# PowerSupplies.net
KiCad netlist of a schematic drawn in Altium Designer
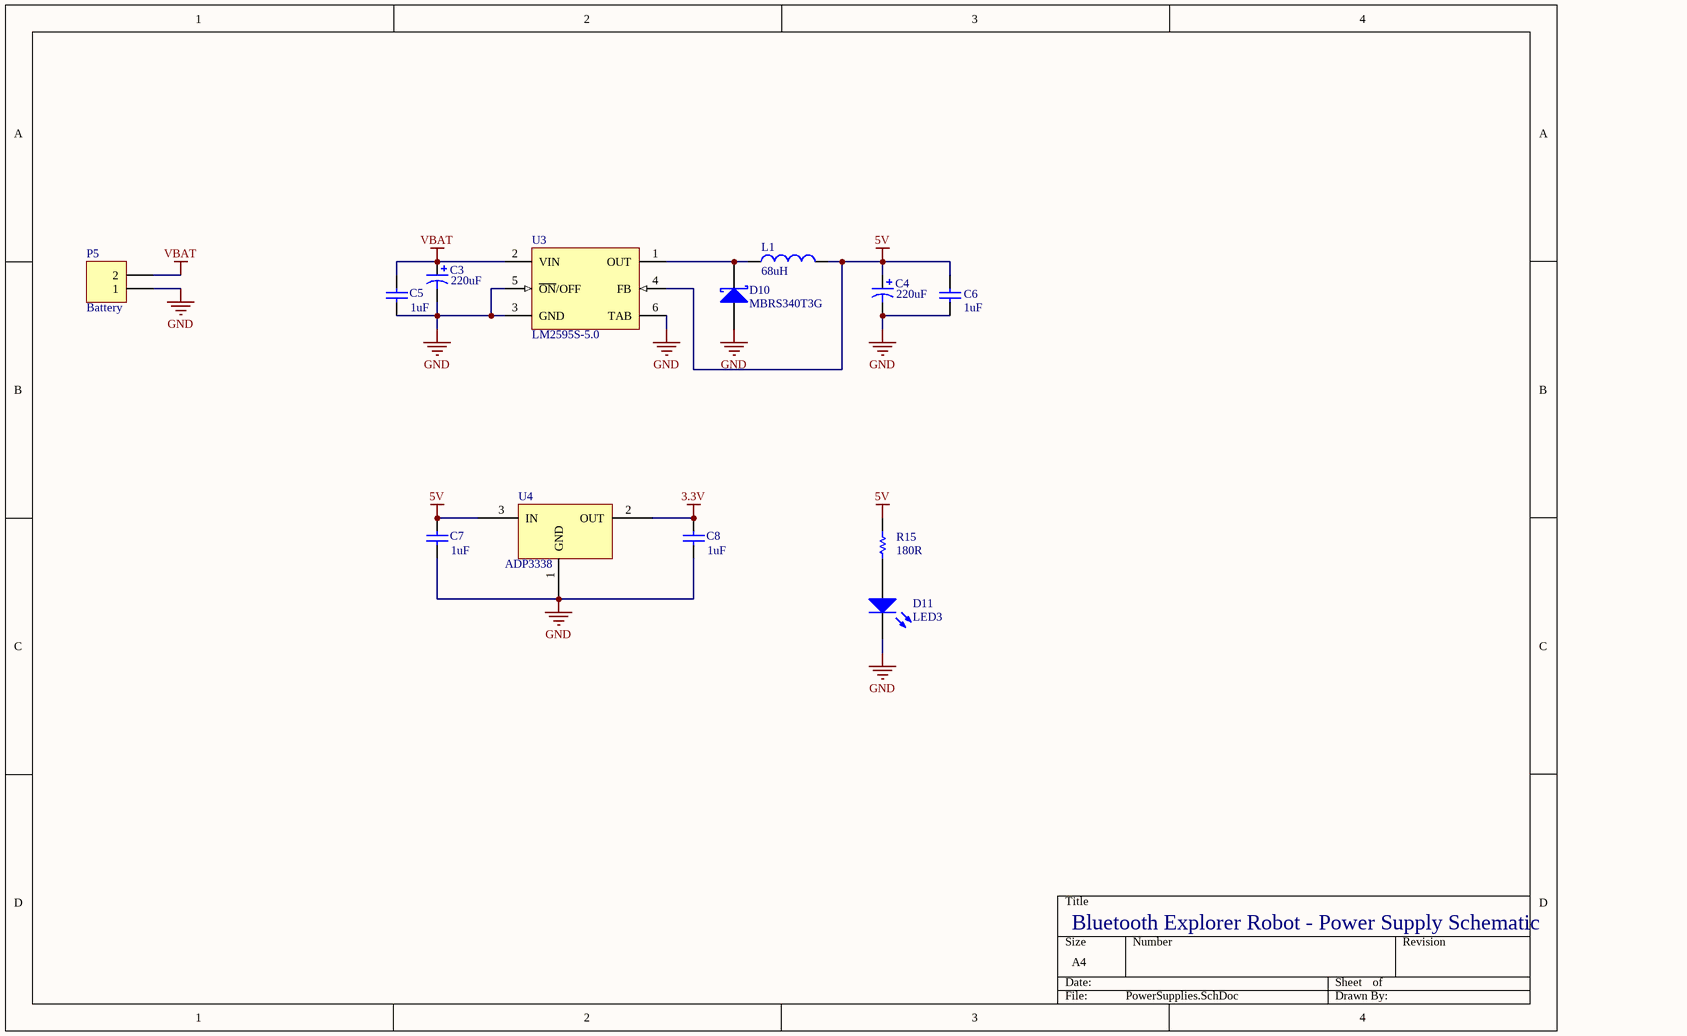
[diagram p0: PowerSupplies.SchDoc]

(export (version "E")
  (design (tool "Eeschema 10.0.6"))
  (components
    (comp (ref "C3")
      (value "220uF")
      (footprint "Cap F")
      (description "Polarized Capacitor (Radial)")
      (fields (field (name "Comment") "Cap Pol1") (field (name "PUBLISHER") "Altium Limited"))
      (libsource (lib "Miscellaneous Devices") (part "Cap Pol1"))
    )
    (comp (ref "C4")
      (value "220uF")
      (footprint "Cap F")
      (description "Polarized Capacitor (Radial)")
      (fields (field (name "Comment") "Cap Pol1") (field (name "PUBLISHER") "Altium Limited"))
      (libsource (lib "Miscellaneous Devices") (part "Cap Pol1"))
    )
    (comp (ref "C5")
      (value "1uF")
      (footprint "C0805")
      (description "Capacitor (Semiconductor SIM Model)")
      (fields (field (name "Comment") "Cap Semi") (field (name "PUBLISHER") "Altium Limited"))
      (libsource (lib "Miscellaneous Devices") (part "Cap Semi"))
    )
    (comp (ref "C6")
      (value "1uF")
      (footprint "C0805")
      (description "Capacitor (Semiconductor SIM Model)")
      (fields (field (name "Comment") "Cap Semi") (field (name "PUBLISHER") "Altium Limited"))
      (libsource (lib "Miscellaneous Devices") (part "Cap Semi"))
    )
    (comp (ref "C7")
      (value "1uF")
      (footprint "C0805")
      (description "Capacitor (Semiconductor SIM Model)")
      (fields (field (name "Comment") "Cap Semi") (field (name "PUBLISHER") "Altium Limited"))
      (libsource (lib "Miscellaneous Devices") (part "Cap Semi"))
    )
    (comp (ref "C8")
      (value "1uF")
      (footprint "C0805")
      (description "Capacitor (Semiconductor SIM Model)")
      (fields (field (name "Comment") "Cap Semi") (field (name "PUBLISHER") "Altium Limited"))
      (libsource (lib "Miscellaneous Devices") (part "Cap Semi"))
    )
    (comp (ref "D10")
      (value "MBRS340T3G")
      (footprint "SMC")
      (description "Schottky Diode")
      (fields (field (name "PUBLISHER") "Altium Limited"))
      (libsource (lib "Miscellaneous Devices") (part "D Schottky"))
    )
    (comp (ref "D11")
      (value "LED3")
      (footprint "DSO-C2/D5.6")
      (description "Typical BLUE SiC LED")
      (fields (field (name "PUBLISHER") "Altium Limited"))
      (libsource (lib "Miscellaneous Devices") (part "LED3"))
    )
    (comp (ref "L1")
      (value "68uH")
      (footprint "inductor_epcos")
      (description "Inductor")
      (fields (field (name "PUBLISHER") "Altium Limited"))
      (libsource (lib "Miscellaneous Devices") (part "Inductor"))
    )
    (comp (ref "P5")
      (value "Battery")
      (footprint "PCB Screw Connector")
      (description "Header, 2-Pin")
      (fields (field (name "PUBLISHER") "Altium Limited"))
      (libsource (lib "Miscellaneous Connectors") (part "Header 2"))
    )
    (comp (ref "R15")
      (value "180R")
      (footprint "2012[0805]")
      (description "Semiconductor Resistor")
      (fields (field (name "Comment") "Res Semi") (field (name "PUBLISHER") "Altium Limited"))
      (libsource (lib "Miscellaneous Devices") (part "Res Semi"))
    )
    (comp (ref "U3")
      (value "LM2595S-5.0")
      (footprint "TS5B_N")
      (description "SIMPLE SWITCHER Power Converter 150 KHz 1A Step-Down Voltage Regulator")
      (fields
        (field (name "MANUFACTURER") "National Semiconductor")
        (field (name "DIGIKEYPARTNUMBER") "LM2595S-5.0-ND")
        (field (name "PUBLISHER") "Altium Limited")
      )
      (libsource (lib "NSC Switcher") (part "LM2595S-5.0"))
    )
    (comp (ref "U4")
      (value "ADP3338")
      (footprint "Miscellaneous Devices:SOT223-4l")
      (libsource (lib "MiscParts") (part "ADP3338"))
    )
  )
  (nets
    (net (code "1") (name "3.3V") (class "Default")
      (node (ref "C8") (pin "2") (pinfunction "2_2") (pintype "passive"))
      (node (ref "U4") (pin "2") (pinfunction "OUT_2") (pintype "passive"))
    )
    (net (code "2") (name "5V") (class "Default")
      (node (ref "C4") (pin "1") (pinfunction "1_1") (pintype "passive"))
      (node (ref "C6") (pin "2") (pinfunction "2_2") (pintype "passive"))
      (node (ref "C7") (pin "2") (pinfunction "2_2") (pintype "passive"))
      (node (ref "L1") (pin "2") (pinfunction "2_2") (pintype "passive"))
      (node (ref "R15") (pin "2") (pinfunction "2_2") (pintype "passive"))
      (node (ref "U3") (pin "4") (pinfunction "FB_4") (pintype "input"))
      (node (ref "U4") (pin "3") (pinfunction "IN_3") (pintype "passive"))
    )
    (net (code "3") (name "GND") (class "Default")
      (node (ref "C3") (pin "2") (pinfunction "2_2") (pintype "passive"))
      (node (ref "C4") (pin "2") (pinfunction "2_2") (pintype "passive"))
      (node (ref "C5") (pin "1") (pinfunction "1_1") (pintype "passive"))
      (node (ref "C6") (pin "1") (pinfunction "1_1") (pintype "passive"))
      (node (ref "C7") (pin "1") (pinfunction "1_1") (pintype "passive"))
      (node (ref "C8") (pin "1") (pinfunction "1_1") (pintype "passive"))
      (node (ref "D10") (pin "1") (pinfunction "A_1") (pintype "passive"))
      (node (ref "D11") (pin "2") (pinfunction "K_2") (pintype "passive"))
      (node (ref "P5") (pin "1") (pinfunction "1_1") (pintype "passive"))
      (node (ref "U3") (pin "3") (pinfunction "GND_3") (pintype "power_in"))
      (node (ref "U3") (pin "5") (pinfunction "~{ON}/OFF_5") (pintype "input"))
      (node (ref "U3") (pin "6") (pinfunction "TAB_6") (pintype "power_in"))
      (node (ref "U4") (pin "1") (pinfunction "GND_1") (pintype "passive"))
    )
    (net (code "4") (name "Net-(D10-K)") (class "Default")
      (node (ref "D10") (pin "2") (pinfunction "K_2") (pintype "passive"))
      (node (ref "L1") (pin "1") (pinfunction "1_1") (pintype "passive"))
      (node (ref "U3") (pin "1") (pinfunction "OUT_1") (pintype "power_in"))
    )
    (net (code "5") (name "Net-(D11-A)") (class "Default")
      (node (ref "D11") (pin "1") (pinfunction "A_1") (pintype "passive"))
      (node (ref "R15") (pin "1") (pinfunction "1_1") (pintype "passive"))
    )
    (net (code "6") (name "VBAT") (class "Default")
      (node (ref "C3") (pin "1") (pinfunction "1_1") (pintype "passive"))
      (node (ref "C5") (pin "2") (pinfunction "2_2") (pintype "passive"))
      (node (ref "P5") (pin "2") (pinfunction "2_2") (pintype "passive"))
      (node (ref "U3") (pin "2") (pinfunction "VIN_2") (pintype "power_in"))
    )
  )
)
